# Chip_Apple_Power.net
KiCad netlist of a schematic drawn in EAGLE
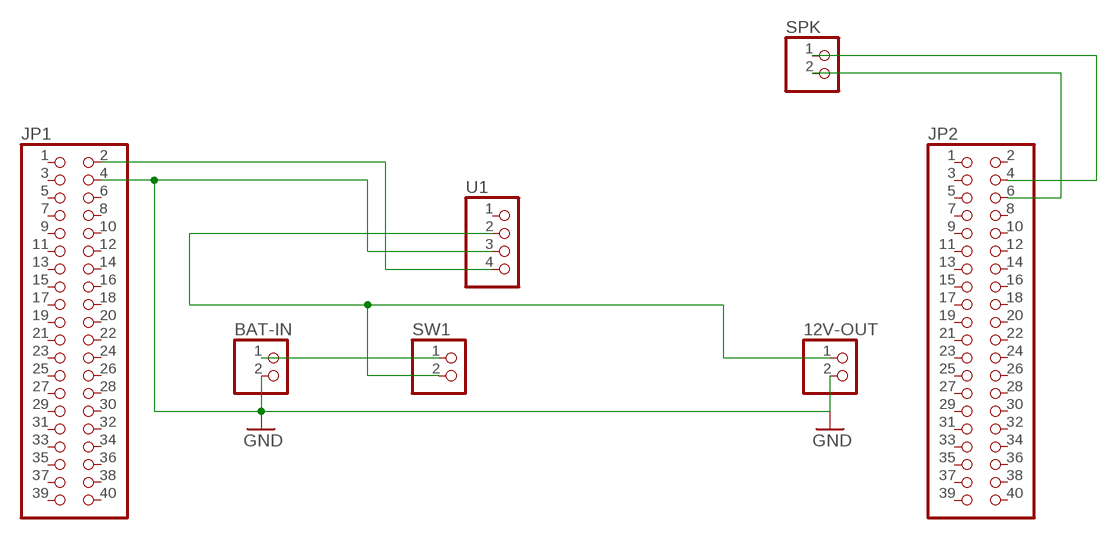
[diagram p0: schematic, sheet 1]

(export (version "E")
  (design (tool "Eeschema 10.0.6"))
  (components
    (comp (ref "12V-OUT")
      (value "PINHD-1X2")
      (footprint "eagle-import:1X02")
      (libsource (lib "eagle-import") (part "PINHD-1X2"))
    )
    (comp (ref "BAT-IN")
      (value "PINHD-1X2")
      (footprint "eagle-import:1X02")
      (libsource (lib "eagle-import") (part "PINHD-1X2"))
    )
    (comp (ref "JP1")
      (value "PINHD-2X20")
      (footprint "eagle-import:2X20")
      (libsource (lib "eagle-import") (part "PINHD-2X20"))
    )
    (comp (ref "JP2")
      (value "PINHD-2X20")
      (footprint "eagle-import:2X20")
      (libsource (lib "eagle-import") (part "PINHD-2X20"))
    )
    (comp (ref "SPK")
      (value "PINHD-1X2")
      (footprint "eagle-import:1X02")
      (libsource (lib "eagle-import") (part "PINHD-1X2"))
    )
    (comp (ref "SW1")
      (value "PINHD-1X2")
      (footprint "eagle-import:1X02")
      (libsource (lib "eagle-import") (part "PINHD-1X2"))
    )
    (comp (ref "U1")
      (value "PINHD-1X4/90")
      (footprint "eagle-import:1X04_90")
      (libsource (lib "eagle-import") (part "PINHD-1X4/90"))
    )
  )
  (nets
    (net (code "1") (name "GND") (class "Default")
      (node (ref "12V-OUT") (pin "2") (pinfunction "2_2") (pintype "passive"))
      (node (ref "BAT-IN") (pin "2") (pinfunction "2_2") (pintype "passive"))
      (node (ref "JP1") (pin "4") (pinfunction "4_4") (pintype "passive"))
      (node (ref "U1") (pin "3") (pinfunction "3_3") (pintype "passive"))
    )
    (net (code "2") (name "Net-(12V-OUT-Pad1)") (class "Default")
      (node (ref "12V-OUT") (pin "1") (pinfunction "1_1") (pintype "passive"))
      (node (ref "SW1") (pin "2") (pinfunction "2_2") (pintype "passive"))
      (node (ref "U1") (pin "2") (pinfunction "2_2") (pintype "passive"))
    )
    (net (code "3") (name "Net-(BAT-IN-Pad1)") (class "Default")
      (node (ref "BAT-IN") (pin "1") (pinfunction "1_1") (pintype "passive"))
      (node (ref "SW1") (pin "1") (pinfunction "1_1") (pintype "passive"))
    )
    (net (code "4") (name "Net-(JP1-Pad2)") (class "Default")
      (node (ref "JP1") (pin "2") (pinfunction "2_2") (pintype "passive"))
      (node (ref "U1") (pin "4") (pinfunction "4_4") (pintype "passive"))
    )
    (net (code "5") (name "Net-(JP2-Pad4)") (class "Default")
      (node (ref "JP2") (pin "4") (pinfunction "4_4") (pintype "passive"))
      (node (ref "SPK") (pin "1") (pinfunction "1_1") (pintype "passive"))
    )
    (net (code "6") (name "Net-(JP2-Pad6)") (class "Default")
      (node (ref "JP2") (pin "6") (pinfunction "6_6") (pintype "passive"))
      (node (ref "SPK") (pin "2") (pinfunction "2_2") (pintype "passive"))
    )
    (net (code "7") (name "unconnected-(JP1-Pad1)") (class "Default")
      (node (ref "JP1") (pin "1") (pinfunction "1_1") (pintype "passive"))
    )
    (net (code "8") (name "unconnected-(JP1-Pad3)") (class "Default")
      (node (ref "JP1") (pin "3") (pinfunction "3_3") (pintype "passive"))
    )
    (net (code "9") (name "unconnected-(JP1-Pad5)") (class "Default")
      (node (ref "JP1") (pin "5") (pinfunction "5_5") (pintype "passive"))
    )
    (net (code "10") (name "unconnected-(JP1-Pad6)") (class "Default")
      (node (ref "JP1") (pin "6") (pinfunction "6_6") (pintype "passive"))
    )
    (net (code "11") (name "unconnected-(JP1-Pad7)") (class "Default")
      (node (ref "JP1") (pin "7") (pinfunction "7_7") (pintype "passive"))
    )
    (net (code "12") (name "unconnected-(JP1-Pad8)") (class "Default")
      (node (ref "JP1") (pin "8") (pinfunction "8_8") (pintype "passive"))
    )
    (net (code "13") (name "unconnected-(JP1-Pad9)") (class "Default")
      (node (ref "JP1") (pin "9") (pinfunction "9_9") (pintype "passive"))
    )
    (net (code "14") (name "unconnected-(JP1-Pad10)") (class "Default")
      (node (ref "JP1") (pin "10") (pinfunction "10_10") (pintype "passive"))
    )
    (net (code "15") (name "unconnected-(JP1-Pad11)") (class "Default")
      (node (ref "JP1") (pin "11") (pinfunction "11_11") (pintype "passive"))
    )
    (net (code "16") (name "unconnected-(JP1-Pad12)") (class "Default")
      (node (ref "JP1") (pin "12") (pinfunction "12_12") (pintype "passive"))
    )
    (net (code "17") (name "unconnected-(JP1-Pad13)") (class "Default")
      (node (ref "JP1") (pin "13") (pinfunction "13_13") (pintype "passive"))
    )
    (net (code "18") (name "unconnected-(JP1-Pad14)") (class "Default")
      (node (ref "JP1") (pin "14") (pinfunction "14_14") (pintype "passive"))
    )
    (net (code "19") (name "unconnected-(JP1-Pad15)") (class "Default")
      (node (ref "JP1") (pin "15") (pinfunction "15_15") (pintype "passive"))
    )
    (net (code "20") (name "unconnected-(JP1-Pad16)") (class "Default")
      (node (ref "JP1") (pin "16") (pinfunction "16_16") (pintype "passive"))
    )
    (net (code "21") (name "unconnected-(JP1-Pad17)") (class "Default")
      (node (ref "JP1") (pin "17") (pinfunction "17_17") (pintype "passive"))
    )
    (net (code "22") (name "unconnected-(JP1-Pad18)") (class "Default")
      (node (ref "JP1") (pin "18") (pinfunction "18_18") (pintype "passive"))
    )
    (net (code "23") (name "unconnected-(JP1-Pad19)") (class "Default")
      (node (ref "JP1") (pin "19") (pinfunction "19_19") (pintype "passive"))
    )
    (net (code "24") (name "unconnected-(JP1-Pad20)") (class "Default")
      (node (ref "JP1") (pin "20") (pinfunction "20_20") (pintype "passive"))
    )
    (net (code "25") (name "unconnected-(JP1-Pad21)") (class "Default")
      (node (ref "JP1") (pin "21") (pinfunction "21_21") (pintype "passive"))
    )
    (net (code "26") (name "unconnected-(JP1-Pad22)") (class "Default")
      (node (ref "JP1") (pin "22") (pinfunction "22_22") (pintype "passive"))
    )
    (net (code "27") (name "unconnected-(JP1-Pad23)") (class "Default")
      (node (ref "JP1") (pin "23") (pinfunction "23_23") (pintype "passive"))
    )
    (net (code "28") (name "unconnected-(JP1-Pad24)") (class "Default")
      (node (ref "JP1") (pin "24") (pinfunction "24_24") (pintype "passive"))
    )
    (net (code "29") (name "unconnected-(JP1-Pad25)") (class "Default")
      (node (ref "JP1") (pin "25") (pinfunction "25_25") (pintype "passive"))
    )
    (net (code "30") (name "unconnected-(JP1-Pad26)") (class "Default")
      (node (ref "JP1") (pin "26") (pinfunction "26_26") (pintype "passive"))
    )
    (net (code "31") (name "unconnected-(JP1-Pad27)") (class "Default")
      (node (ref "JP1") (pin "27") (pinfunction "27_27") (pintype "passive"))
    )
    (net (code "32") (name "unconnected-(JP1-Pad28)") (class "Default")
      (node (ref "JP1") (pin "28") (pinfunction "28_28") (pintype "passive"))
    )
    (net (code "33") (name "unconnected-(JP1-Pad29)") (class "Default")
      (node (ref "JP1") (pin "29") (pinfunction "29_29") (pintype "passive"))
    )
    (net (code "34") (name "unconnected-(JP1-Pad30)") (class "Default")
      (node (ref "JP1") (pin "30") (pinfunction "30_30") (pintype "passive"))
    )
    (net (code "35") (name "unconnected-(JP1-Pad31)") (class "Default")
      (node (ref "JP1") (pin "31") (pinfunction "31_31") (pintype "passive"))
    )
    (net (code "36") (name "unconnected-(JP1-Pad32)") (class "Default")
      (node (ref "JP1") (pin "32") (pinfunction "32_32") (pintype "passive"))
    )
    (net (code "37") (name "unconnected-(JP1-Pad33)") (class "Default")
      (node (ref "JP1") (pin "33") (pinfunction "33_33") (pintype "passive"))
    )
    (net (code "38") (name "unconnected-(JP1-Pad34)") (class "Default")
      (node (ref "JP1") (pin "34") (pinfunction "34_34") (pintype "passive"))
    )
    (net (code "39") (name "unconnected-(JP1-Pad35)") (class "Default")
      (node (ref "JP1") (pin "35") (pinfunction "35_35") (pintype "passive"))
    )
    (net (code "40") (name "unconnected-(JP1-Pad36)") (class "Default")
      (node (ref "JP1") (pin "36") (pinfunction "36_36") (pintype "passive"))
    )
    (net (code "41") (name "unconnected-(JP1-Pad37)") (class "Default")
      (node (ref "JP1") (pin "37") (pinfunction "37_37") (pintype "passive"))
    )
    (net (code "42") (name "unconnected-(JP1-Pad38)") (class "Default")
      (node (ref "JP1") (pin "38") (pinfunction "38_38") (pintype "passive"))
    )
    (net (code "43") (name "unconnected-(JP1-Pad39)") (class "Default")
      (node (ref "JP1") (pin "39") (pinfunction "39_39") (pintype "passive"))
    )
    (net (code "44") (name "unconnected-(JP1-Pad40)") (class "Default")
      (node (ref "JP1") (pin "40") (pinfunction "40_40") (pintype "passive"))
    )
    (net (code "45") (name "unconnected-(JP2-Pad1)") (class "Default")
      (node (ref "JP2") (pin "1") (pinfunction "1_1") (pintype "passive"))
    )
    (net (code "46") (name "unconnected-(JP2-Pad2)") (class "Default")
      (node (ref "JP2") (pin "2") (pinfunction "2_2") (pintype "passive"))
    )
    (net (code "47") (name "unconnected-(JP2-Pad3)") (class "Default")
      (node (ref "JP2") (pin "3") (pinfunction "3_3") (pintype "passive"))
    )
    (net (code "48") (name "unconnected-(JP2-Pad5)") (class "Default")
      (node (ref "JP2") (pin "5") (pinfunction "5_5") (pintype "passive"))
    )
    (net (code "49") (name "unconnected-(JP2-Pad7)") (class "Default")
      (node (ref "JP2") (pin "7") (pinfunction "7_7") (pintype "passive"))
    )
    (net (code "50") (name "unconnected-(JP2-Pad8)") (class "Default")
      (node (ref "JP2") (pin "8") (pinfunction "8_8") (pintype "passive"))
    )
    (net (code "51") (name "unconnected-(JP2-Pad9)") (class "Default")
      (node (ref "JP2") (pin "9") (pinfunction "9_9") (pintype "passive"))
    )
    (net (code "52") (name "unconnected-(JP2-Pad10)") (class "Default")
      (node (ref "JP2") (pin "10") (pinfunction "10_10") (pintype "passive"))
    )
    (net (code "53") (name "unconnected-(JP2-Pad11)") (class "Default")
      (node (ref "JP2") (pin "11") (pinfunction "11_11") (pintype "passive"))
    )
    (net (code "54") (name "unconnected-(JP2-Pad12)") (class "Default")
      (node (ref "JP2") (pin "12") (pinfunction "12_12") (pintype "passive"))
    )
    (net (code "55") (name "unconnected-(JP2-Pad13)") (class "Default")
      (node (ref "JP2") (pin "13") (pinfunction "13_13") (pintype "passive"))
    )
    (net (code "56") (name "unconnected-(JP2-Pad14)") (class "Default")
      (node (ref "JP2") (pin "14") (pinfunction "14_14") (pintype "passive"))
    )
    (net (code "57") (name "unconnected-(JP2-Pad15)") (class "Default")
      (node (ref "JP2") (pin "15") (pinfunction "15_15") (pintype "passive"))
    )
    (net (code "58") (name "unconnected-(JP2-Pad16)") (class "Default")
      (node (ref "JP2") (pin "16") (pinfunction "16_16") (pintype "passive"))
    )
    (net (code "59") (name "unconnected-(JP2-Pad17)") (class "Default")
      (node (ref "JP2") (pin "17") (pinfunction "17_17") (pintype "passive"))
    )
    (net (code "60") (name "unconnected-(JP2-Pad18)") (class "Default")
      (node (ref "JP2") (pin "18") (pinfunction "18_18") (pintype "passive"))
    )
    (net (code "61") (name "unconnected-(JP2-Pad19)") (class "Default")
      (node (ref "JP2") (pin "19") (pinfunction "19_19") (pintype "passive"))
    )
    (net (code "62") (name "unconnected-(JP2-Pad20)") (class "Default")
      (node (ref "JP2") (pin "20") (pinfunction "20_20") (pintype "passive"))
    )
    (net (code "63") (name "unconnected-(JP2-Pad21)") (class "Default")
      (node (ref "JP2") (pin "21") (pinfunction "21_21") (pintype "passive"))
    )
    (net (code "64") (name "unconnected-(JP2-Pad22)") (class "Default")
      (node (ref "JP2") (pin "22") (pinfunction "22_22") (pintype "passive"))
    )
    (net (code "65") (name "unconnected-(JP2-Pad23)") (class "Default")
      (node (ref "JP2") (pin "23") (pinfunction "23_23") (pintype "passive"))
    )
    (net (code "66") (name "unconnected-(JP2-Pad24)") (class "Default")
      (node (ref "JP2") (pin "24") (pinfunction "24_24") (pintype "passive"))
    )
    (net (code "67") (name "unconnected-(JP2-Pad25)") (class "Default")
      (node (ref "JP2") (pin "25") (pinfunction "25_25") (pintype "passive"))
    )
    (net (code "68") (name "unconnected-(JP2-Pad26)") (class "Default")
      (node (ref "JP2") (pin "26") (pinfunction "26_26") (pintype "passive"))
    )
    (net (code "69") (name "unconnected-(JP2-Pad27)") (class "Default")
      (node (ref "JP2") (pin "27") (pinfunction "27_27") (pintype "passive"))
    )
    (net (code "70") (name "unconnected-(JP2-Pad28)") (class "Default")
      (node (ref "JP2") (pin "28") (pinfunction "28_28") (pintype "passive"))
    )
    (net (code "71") (name "unconnected-(JP2-Pad29)") (class "Default")
      (node (ref "JP2") (pin "29") (pinfunction "29_29") (pintype "passive"))
    )
    (net (code "72") (name "unconnected-(JP2-Pad30)") (class "Default")
      (node (ref "JP2") (pin "30") (pinfunction "30_30") (pintype "passive"))
    )
    (net (code "73") (name "unconnected-(JP2-Pad31)") (class "Default")
      (node (ref "JP2") (pin "31") (pinfunction "31_31") (pintype "passive"))
    )
    (net (code "74") (name "unconnected-(JP2-Pad32)") (class "Default")
      (node (ref "JP2") (pin "32") (pinfunction "32_32") (pintype "passive"))
    )
    (net (code "75") (name "unconnected-(JP2-Pad33)") (class "Default")
      (node (ref "JP2") (pin "33") (pinfunction "33_33") (pintype "passive"))
    )
    (net (code "76") (name "unconnected-(JP2-Pad34)") (class "Default")
      (node (ref "JP2") (pin "34") (pinfunction "34_34") (pintype "passive"))
    )
    (net (code "77") (name "unconnected-(JP2-Pad35)") (class "Default")
      (node (ref "JP2") (pin "35") (pinfunction "35_35") (pintype "passive"))
    )
    (net (code "78") (name "unconnected-(JP2-Pad36)") (class "Default")
      (node (ref "JP2") (pin "36") (pinfunction "36_36") (pintype "passive"))
    )
    (net (code "79") (name "unconnected-(JP2-Pad37)") (class "Default")
      (node (ref "JP2") (pin "37") (pinfunction "37_37") (pintype "passive"))
    )
    (net (code "80") (name "unconnected-(JP2-Pad38)") (class "Default")
      (node (ref "JP2") (pin "38") (pinfunction "38_38") (pintype "passive"))
    )
    (net (code "81") (name "unconnected-(JP2-Pad39)") (class "Default")
      (node (ref "JP2") (pin "39") (pinfunction "39_39") (pintype "passive"))
    )
    (net (code "82") (name "unconnected-(JP2-Pad40)") (class "Default")
      (node (ref "JP2") (pin "40") (pinfunction "40_40") (pintype "passive"))
    )
    (net (code "83") (name "unconnected-(U1-Pad1)") (class "Default")
      (node (ref "U1") (pin "1") (pinfunction "1_1") (pintype "passive"))
    )
  )
)
